# Keyfinder_Alert.net
KiCad netlist of a schematic drawn in Altium Designer
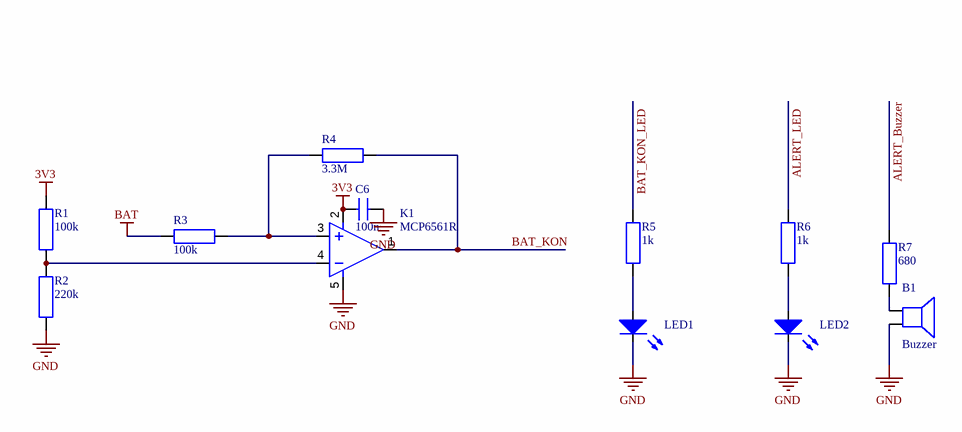
[diagram p0: Keyfinder_Alert.SchDoc]

(export (version "E")
  (design (tool "Eeschema 10.0.6"))
  (components
    (comp (ref "B1")
      (value "Buzzer")
      (footprint "piezo_ele")
      (libsource (lib "DEVICE_HSLU") (part "SPEAKER"))
    )
    (comp (ref "C6")
      (value "100n")
      (footprint "0805_C")
      (description "Normaler Kondensator")
      (libsource (lib "MainBoard") (part "C?"))
    )
    (comp (ref "K1") (value "MCP6561R") (footprint "SOT23-5") (libsource (lib "MainBoard") (part "OPAMP")))
    (comp (ref "LED1") (value "~") (footprint "0805_LED") (libsource (lib "Sch_Lib") (part "LED")))
    (comp (ref "LED2") (value "~") (footprint "0805_LED") (libsource (lib "Sch_Lib") (part "LED")))
    (comp (ref "R1")
      (value "100k")
      (footprint "0805_R")
      (description "Normaler Widerstand")
      (libsource (lib "MainBoard") (part "R?"))
    )
    (comp (ref "R2")
      (value "220k")
      (footprint "0805_R")
      (description "Normaler Widerstand")
      (libsource (lib "MainBoard") (part "R?"))
    )
    (comp (ref "R3")
      (value "100k")
      (footprint "0805_R")
      (description "Normaler Widerstand")
      (libsource (lib "MainBoard") (part "R?"))
    )
    (comp (ref "R4")
      (value "3.3M")
      (footprint "0805_R")
      (description "Normaler Widerstand")
      (libsource (lib "MainBoard") (part "R?"))
    )
    (comp (ref "R5")
      (value "1k")
      (footprint "0805_R")
      (description "Normaler Widerstand")
      (libsource (lib "MainBoard") (part "R?"))
    )
    (comp (ref "R6")
      (value "1k")
      (footprint "0805_R")
      (description "Normaler Widerstand")
      (libsource (lib "MainBoard") (part "R?"))
    )
    (comp (ref "R7")
      (value "680")
      (footprint "0805_R")
      (description "Normaler Widerstand")
      (libsource (lib "MainBoard") (part "R?"))
    )
  )
  (nets
    (net (code "1") (name "/ALERT_Buzzer") (class "Default") (node (ref "R7") (pin "1") (pintype "passive")))
    (net (code "2") (name "/ALERT_LED") (class "Default") (node (ref "R6") (pin "1") (pintype "passive")))
    (net (code "3") (name "/BAT_KON") (class "Default")
      (node (ref "K1") (pin "1") (pinfunction "1_1") (pintype "passive"))
      (node (ref "R4") (pin "1") (pintype "passive"))
    )
    (net (code "4") (name "/BAT_KON_LED") (class "Default") (node (ref "R5") (pin "1") (pintype "passive")))
    (net (code "5") (name "3V3") (class "Default")
      (node (ref "C6") (pin "2") (pinfunction "2_2") (pintype "passive"))
      (node (ref "K1") (pin "2") (pinfunction "2_2") (pintype "passive"))
      (node (ref "R1") (pin "1") (pintype "passive"))
    )
    (net (code "6") (name "BAT") (class "Default") (node (ref "R3") (pin "2") (pintype "passive")))
    (net (code "7") (name "GND") (class "Default")
      (node (ref "B1") (pin "2") (pintype "passive"))
      (node (ref "C6") (pin "1") (pinfunction "1_1") (pintype "passive"))
      (node (ref "K1") (pin "5") (pinfunction "5_5") (pintype "passive"))
      (node (ref "LED1") (pin "2") (pinfunction "K_2") (pintype "passive"))
      (node (ref "LED2") (pin "2") (pinfunction "K_2") (pintype "passive"))
      (node (ref "R2") (pin "2") (pintype "passive"))
    )
    (net (code "8") (name "Net-(B1-Pad1)") (class "Default")
      (node (ref "B1") (pin "1") (pintype "passive"))
      (node (ref "R7") (pin "2") (pintype "passive"))
    )
    (net (code "9") (name "Net-(K1-Pad3)") (class "Default")
      (node (ref "K1") (pin "3") (pinfunction "3_3") (pintype "passive"))
      (node (ref "R3") (pin "1") (pintype "passive"))
      (node (ref "R4") (pin "2") (pintype "passive"))
    )
    (net (code "10") (name "Net-(K1-Pad4)") (class "Default")
      (node (ref "K1") (pin "4") (pinfunction "4_4") (pintype "passive"))
      (node (ref "R1") (pin "2") (pintype "passive"))
      (node (ref "R2") (pin "1") (pintype "passive"))
    )
    (net (code "11") (name "Net-(LED1-A)") (class "Default")
      (node (ref "LED1") (pin "1") (pinfunction "A_1") (pintype "passive"))
      (node (ref "R5") (pin "2") (pintype "passive"))
    )
    (net (code "12") (name "Net-(LED2-A)") (class "Default")
      (node (ref "LED2") (pin "1") (pinfunction "A_1") (pintype "passive"))
      (node (ref "R6") (pin "2") (pintype "passive"))
    )
  )
)
